# MI0283QT_v15.net
KiCad netlist of a schematic drawn in EAGLE
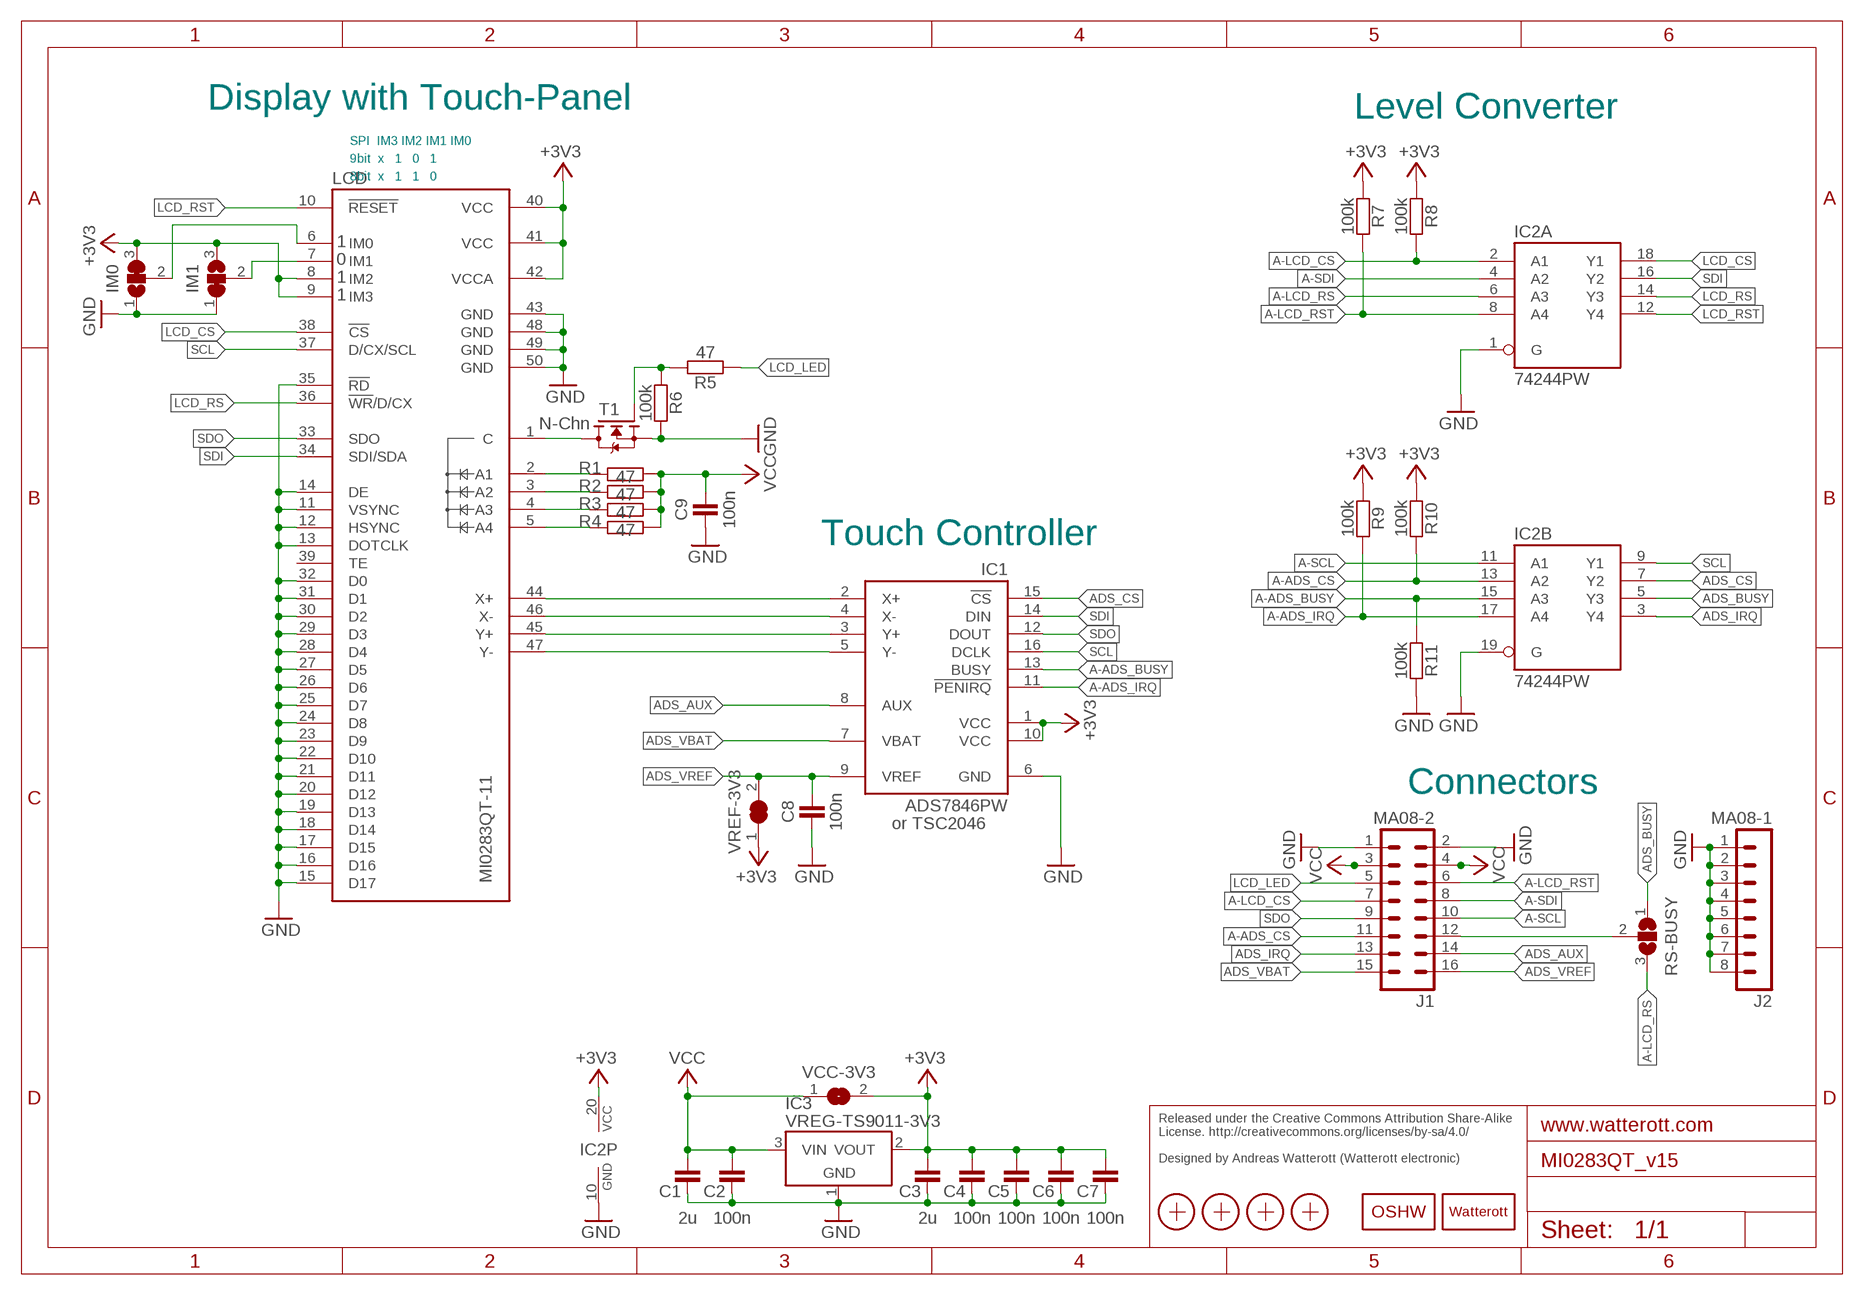
[diagram p0: schematic, sheet 1]

(export (version "E")
  (design (tool "Eeschema 10.0.6"))
  (components
    (comp (ref "C1")
      (value "2u")
      (footprint "eagle-import:C0603")
      (libsource (lib "eagle-import") (part "CAPACITOR-0603"))
    )
    (comp (ref "C2")
      (value "100n")
      (footprint "eagle-import:C0402")
      (libsource (lib "eagle-import") (part "CAPACITOR-0402"))
    )
    (comp (ref "C3")
      (value "2u")
      (footprint "eagle-import:C0603")
      (libsource (lib "eagle-import") (part "CAPACITOR-0603"))
    )
    (comp (ref "C4")
      (value "100n")
      (footprint "eagle-import:C0402")
      (libsource (lib "eagle-import") (part "CAPACITOR-0402"))
    )
    (comp (ref "C5")
      (value "100n")
      (footprint "eagle-import:C0402")
      (libsource (lib "eagle-import") (part "CAPACITOR-0402"))
    )
    (comp (ref "C6")
      (value "100n")
      (footprint "eagle-import:C0402")
      (libsource (lib "eagle-import") (part "CAPACITOR-0402"))
    )
    (comp (ref "C7")
      (value "100n")
      (footprint "eagle-import:C0402")
      (libsource (lib "eagle-import") (part "CAPACITOR-0402"))
    )
    (comp (ref "C8")
      (value "100n")
      (footprint "eagle-import:C0402")
      (libsource (lib "eagle-import") (part "CAPACITOR-0402"))
    )
    (comp (ref "C9")
      (value "100n")
      (footprint "eagle-import:C0402")
      (libsource (lib "eagle-import") (part "CAPACITOR-0402"))
    )
    (comp (ref "IC1")
      (value "ADS7846PW")
      (footprint "eagle-import:TSSOP16")
      (libsource (lib "eagle-import") (part "ADS7846PW"))
    )
    (comp (ref "IC2")
      (value "74244PW")
      (footprint "eagle-import:TSSOP20")
      (libsource (lib "eagle-import") (part "74244PWLVC"))
    )
    (comp (ref "IC3")
      (value "VREG-TS9011-3V3")
      (footprint "eagle-import:SOT23")
      (libsource (lib "eagle-import") (part "VREG-TS9011-3V3"))
    )
    (comp (ref "IM0")
      (value "JUMPER3-0603")
      (footprint "eagle-import:JUMPER3-0603")
      (libsource (lib "eagle-import") (part "JUMPER3-0603"))
    )
    (comp (ref "IM1")
      (value "JUMPER3-0603")
      (footprint "eagle-import:JUMPER3-0603")
      (libsource (lib "eagle-import") (part "JUMPER3-0603"))
    )
    (comp (ref "J1")
      (value "MA08-2")
      (footprint "eagle-import:MA08-2")
      (libsource (lib "eagle-import") (part "MA08-2"))
    )
    (comp (ref "J2")
      (value "MA08-1")
      (footprint "eagle-import:MA08-1")
      (libsource (lib "eagle-import") (part "MA08-1"))
    )
    (comp (ref "LCD")
      (value "MI0283QT-11")
      (footprint "eagle-import:MI0283QT11")
      (libsource (lib "eagle-import") (part "MI0283QT-11"))
    )
    (comp (ref "LOGO2")
      (value "OSHW_LOGOX0150")
      (footprint "eagle-import:OSHW_6X150")
      (libsource (lib "eagle-import") (part "OSHW_LOGOX0150"))
    )
    (comp (ref "LOGO3")
      (value "LOGO-PLACE")
      (footprint "eagle-import:LOGO_TPLACE")
      (libsource (lib "eagle-import") (part "LOGO-PLACE"))
    )
    (comp (ref "R1")
      (value "47")
      (footprint "eagle-import:C0402")
      (libsource (lib "eagle-import") (part "RESISTOR-0402"))
    )
    (comp (ref "R2")
      (value "47")
      (footprint "eagle-import:C0402")
      (libsource (lib "eagle-import") (part "RESISTOR-0402"))
    )
    (comp (ref "R3")
      (value "47")
      (footprint "eagle-import:C0402")
      (libsource (lib "eagle-import") (part "RESISTOR-0402"))
    )
    (comp (ref "R4")
      (value "47")
      (footprint "eagle-import:C0402")
      (libsource (lib "eagle-import") (part "RESISTOR-0402"))
    )
    (comp (ref "R5")
      (value "47")
      (footprint "eagle-import:C0402")
      (libsource (lib "eagle-import") (part "RESISTOR-0402"))
    )
    (comp (ref "R6")
      (value "100k")
      (footprint "eagle-import:C0402")
      (libsource (lib "eagle-import") (part "RESISTOR-0402"))
    )
    (comp (ref "R7")
      (value "100k")
      (footprint "eagle-import:C0402")
      (libsource (lib "eagle-import") (part "RESISTOR-0402"))
    )
    (comp (ref "R8")
      (value "100k")
      (footprint "eagle-import:C0402")
      (libsource (lib "eagle-import") (part "RESISTOR-0402"))
    )
    (comp (ref "R9")
      (value "100k")
      (footprint "eagle-import:C0402")
      (libsource (lib "eagle-import") (part "RESISTOR-0402"))
    )
    (comp (ref "R10")
      (value "100k")
      (footprint "eagle-import:C0402")
      (libsource (lib "eagle-import") (part "RESISTOR-0402"))
    )
    (comp (ref "R11")
      (value "100k")
      (footprint "eagle-import:C0402")
      (libsource (lib "eagle-import") (part "RESISTOR-0402"))
    )
    (comp (ref "RS-BUSY")
      (value "JUMPER3-0603")
      (footprint "eagle-import:JUMPER3-0603")
      (libsource (lib "eagle-import") (part "JUMPER3-0603"))
    )
    (comp (ref "T1")
      (value "N-Chn")
      (footprint "eagle-import:SOT23")
      (libsource (lib "eagle-import") (part "MOSFET-N-SOT23"))
    )
    (comp (ref "VCC-3V3")
      (value "JUMPER2-0603-NC")
      (footprint "eagle-import:JUMPER2-0603_NC")
      (libsource (lib "eagle-import") (part "JUMPER2-0603-NC"))
    )
    (comp (ref "VREF-3V3")
      (value "JUMPER2-0603-NC")
      (footprint "eagle-import:JUMPER2-0603_NC")
      (libsource (lib "eagle-import") (part "JUMPER2-0603-NC"))
    )
    (comp (ref "X1")
      (value "PASSER-07")
      (footprint "eagle-import:PASSER_07MM")
      (libsource (lib "eagle-import") (part "PASSER-07"))
    )
    (comp (ref "X2")
      (value "PASSER-07")
      (footprint "eagle-import:PASSER_07MM")
      (libsource (lib "eagle-import") (part "PASSER-07"))
    )
    (comp (ref "X3")
      (value "PASSER-07")
      (footprint "eagle-import:PASSER_07MM")
      (libsource (lib "eagle-import") (part "PASSER-07"))
    )
    (comp (ref "X4")
      (value "PASSER-07")
      (footprint "eagle-import:PASSER_07MM")
      (libsource (lib "eagle-import") (part "PASSER-07"))
    )
  )
  (nets
    (net (code "1") (name "+3V3") (class "Default")
      (node (ref "C3") (pin "2") (pinfunction "2_2") (pintype "passive"))
      (node (ref "C4") (pin "2") (pinfunction "2_2") (pintype "passive"))
      (node (ref "C5") (pin "2") (pinfunction "2_2") (pintype "passive"))
      (node (ref "C6") (pin "2") (pinfunction "2_2") (pintype "passive"))
      (node (ref "C7") (pin "2") (pinfunction "2_2") (pintype "passive"))
      (node (ref "IC1") (pin "1") (pinfunction "VCC_1") (pintype "power_in"))
      (node (ref "IC1") (pin "10") (pinfunction "VCC_10") (pintype "power_in"))
      (node (ref "IC2") (pin "20") (pinfunction "VCC_20") (pintype "power_in"))
      (node (ref "IC3") (pin "2") (pinfunction "VOUT_2") (pintype "power_in"))
      (node (ref "IM0") (pin "3") (pinfunction "3_3") (pintype "passive"))
      (node (ref "IM1") (pin "3") (pinfunction "3_3") (pintype "passive"))
      (node (ref "LCD") (pin "40") (pinfunction "VCC_40") (pintype "power_in"))
      (node (ref "LCD") (pin "41") (pinfunction "VCC_41") (pintype "power_in"))
      (node (ref "LCD") (pin "42") (pinfunction "VCCA_42") (pintype "power_in"))
      (node (ref "LCD") (pin "8") (pinfunction "IM2_8") (pintype "input"))
      (node (ref "LCD") (pin "9") (pinfunction "IM3_9") (pintype "input"))
      (node (ref "R10") (pin "1") (pinfunction "1_1") (pintype "passive"))
      (node (ref "R7") (pin "1") (pinfunction "1_1") (pintype "passive"))
      (node (ref "R8") (pin "1") (pinfunction "1_1") (pintype "passive"))
      (node (ref "R9") (pin "1") (pinfunction "1_1") (pintype "passive"))
      (node (ref "VCC-3V3") (pin "2") (pinfunction "2_2") (pintype "passive"))
      (node (ref "VREF-3V3") (pin "1") (pinfunction "1_1") (pintype "passive"))
    )
    (net (code "2") (name "A-ADS_BUSY") (class "Default")
      (node (ref "IC1") (pin "13") (pinfunction "BUSY_13") (pintype "output"))
      (node (ref "IC2") (pin "15") (pinfunction "A3_15") (pintype "input"))
      (node (ref "R11") (pin "1") (pinfunction "1_1") (pintype "passive"))
    )
    (net (code "3") (name "A-ADS_CS") (class "Default")
      (node (ref "IC2") (pin "13") (pinfunction "A2_13") (pintype "input"))
      (node (ref "J1") (pin "11") (pinfunction "11_11") (pintype "passive"))
      (node (ref "R10") (pin "2") (pinfunction "2_2") (pintype "passive"))
    )
    (net (code "4") (name "A-ADS_IRQ") (class "Default")
      (node (ref "IC1") (pin "11") (pinfunction "~{PENIRQ}_11") (pintype "output"))
      (node (ref "IC2") (pin "17") (pinfunction "A4_17") (pintype "input"))
      (node (ref "R9") (pin "2") (pinfunction "2_2") (pintype "passive"))
    )
    (net (code "5") (name "A-LCD_CS") (class "Default")
      (node (ref "IC2") (pin "2") (pinfunction "A1_2") (pintype "input"))
      (node (ref "J1") (pin "7") (pinfunction "7_7") (pintype "passive"))
      (node (ref "R8") (pin "2") (pinfunction "2_2") (pintype "passive"))
    )
    (net (code "6") (name "A-LCD_RS") (class "Default")
      (node (ref "IC2") (pin "6") (pinfunction "A3_6") (pintype "input"))
      (node (ref "RS-BUSY") (pin "3") (pinfunction "3_3") (pintype "passive"))
    )
    (net (code "7") (name "A-LCD_RST") (class "Default")
      (node (ref "IC2") (pin "8") (pinfunction "A4_8") (pintype "input"))
      (node (ref "J1") (pin "6") (pinfunction "6_6") (pintype "passive"))
      (node (ref "R7") (pin "2") (pinfunction "2_2") (pintype "passive"))
    )
    (net (code "8") (name "A-SCL") (class "Default")
      (node (ref "IC2") (pin "11") (pinfunction "A1_11") (pintype "input"))
      (node (ref "J1") (pin "10") (pinfunction "10_10") (pintype "passive"))
    )
    (net (code "9") (name "A-SDI") (class "Default")
      (node (ref "IC2") (pin "4") (pinfunction "A2_4") (pintype "input"))
      (node (ref "J1") (pin "8") (pinfunction "8_8") (pintype "passive"))
    )
    (net (code "10") (name "ADS_AUX") (class "Default")
      (node (ref "IC1") (pin "8") (pinfunction "AUX_8") (pintype "input"))
      (node (ref "J1") (pin "14") (pinfunction "14_14") (pintype "passive"))
    )
    (net (code "11") (name "ADS_BUSY") (class "Default")
      (node (ref "IC2") (pin "5") (pinfunction "Y3_5") (pintype "tri_state"))
      (node (ref "RS-BUSY") (pin "1") (pinfunction "1_1") (pintype "passive"))
    )
    (net (code "12") (name "ADS_CS") (class "Default")
      (node (ref "IC1") (pin "15") (pinfunction "~{CS}_15") (pintype "input"))
      (node (ref "IC2") (pin "7") (pinfunction "Y2_7") (pintype "tri_state"))
    )
    (net (code "13") (name "ADS_IRQ") (class "Default")
      (node (ref "IC2") (pin "3") (pinfunction "Y4_3") (pintype "tri_state"))
      (node (ref "J1") (pin "13") (pinfunction "13_13") (pintype "passive"))
    )
    (net (code "14") (name "ADS_VBAT") (class "Default")
      (node (ref "IC1") (pin "7") (pinfunction "VBAT_7") (pintype "input"))
      (node (ref "J1") (pin "15") (pinfunction "15_15") (pintype "passive"))
    )
    (net (code "15") (name "ADS_VREF") (class "Default")
      (node (ref "C8") (pin "2") (pinfunction "2_2") (pintype "passive"))
      (node (ref "IC1") (pin "9") (pinfunction "VREF_9") (pintype "bidirectional"))
      (node (ref "J1") (pin "16") (pinfunction "16_16") (pintype "passive"))
      (node (ref "VREF-3V3") (pin "2") (pinfunction "2_2") (pintype "passive"))
    )
    (net (code "16") (name "GND") (class "Default")
      (node (ref "C1") (pin "1") (pinfunction "1_1") (pintype "passive"))
      (node (ref "C2") (pin "1") (pinfunction "1_1") (pintype "passive"))
      (node (ref "C3") (pin "1") (pinfunction "1_1") (pintype "passive"))
      (node (ref "C4") (pin "1") (pinfunction "1_1") (pintype "passive"))
      (node (ref "C5") (pin "1") (pinfunction "1_1") (pintype "passive"))
      (node (ref "C6") (pin "1") (pinfunction "1_1") (pintype "passive"))
      (node (ref "C7") (pin "1") (pinfunction "1_1") (pintype "passive"))
      (node (ref "C8") (pin "1") (pinfunction "1_1") (pintype "passive"))
      (node (ref "C9") (pin "1") (pinfunction "1_1") (pintype "passive"))
      (node (ref "IC1") (pin "6") (pinfunction "GND_6") (pintype "power_in"))
      (node (ref "IC2") (pin "1") (pinfunction "G_1") (pintype "input"))
      (node (ref "IC2") (pin "10") (pinfunction "GND_10") (pintype "power_in"))
      (node (ref "IC2") (pin "19") (pinfunction "G_19") (pintype "input"))
      (node (ref "IC3") (pin "1") (pinfunction "GND_1") (pintype "power_in"))
      (node (ref "IM0") (pin "1") (pinfunction "1_1") (pintype "passive"))
      (node (ref "IM1") (pin "1") (pinfunction "1_1") (pintype "passive"))
      (node (ref "J1") (pin "1") (pinfunction "1_1") (pintype "passive"))
      (node (ref "J1") (pin "2") (pinfunction "2_2") (pintype "passive"))
      (node (ref "J2") (pin "1") (pinfunction "1_1") (pintype "passive"))
      (node (ref "J2") (pin "2") (pinfunction "2_2") (pintype "passive"))
      (node (ref "J2") (pin "3") (pinfunction "3_3") (pintype "passive"))
      (node (ref "J2") (pin "4") (pinfunction "4_4") (pintype "passive"))
      (node (ref "J2") (pin "5") (pinfunction "5_5") (pintype "passive"))
      (node (ref "J2") (pin "6") (pinfunction "6_6") (pintype "passive"))
      (node (ref "J2") (pin "7") (pinfunction "7_7") (pintype "passive"))
      (node (ref "J2") (pin "8") (pinfunction "8_8") (pintype "passive"))
      (node (ref "LCD") (pin "11") (pinfunction "VSYNC_11") (pintype "input"))
      (node (ref "LCD") (pin "12") (pinfunction "HSYNC_12") (pintype "input"))
      (node (ref "LCD") (pin "13") (pinfunction "DOTCLK_13") (pintype "input"))
      (node (ref "LCD") (pin "14") (pinfunction "DE_14") (pintype "input"))
      (node (ref "LCD") (pin "15") (pinfunction "D17_15") (pintype "input"))
      (node (ref "LCD") (pin "16") (pinfunction "D16_16") (pintype "input"))
      (node (ref "LCD") (pin "17") (pinfunction "D15_17") (pintype "input"))
      (node (ref "LCD") (pin "18") (pinfunction "D14_18") (pintype "input"))
      (node (ref "LCD") (pin "19") (pinfunction "D13_19") (pintype "input"))
      (node (ref "LCD") (pin "20") (pinfunction "D12_20") (pintype "input"))
      (node (ref "LCD") (pin "21") (pinfunction "D11_21") (pintype "input"))
      (node (ref "LCD") (pin "22") (pinfunction "D10_22") (pintype "input"))
      (node (ref "LCD") (pin "23") (pinfunction "D9_23") (pintype "input"))
      (node (ref "LCD") (pin "24") (pinfunction "D8_24") (pintype "input"))
      (node (ref "LCD") (pin "25") (pinfunction "D7_25") (pintype "input"))
      (node (ref "LCD") (pin "26") (pinfunction "D6_26") (pintype "input"))
      (node (ref "LCD") (pin "27") (pinfunction "D5_27") (pintype "input"))
      (node (ref "LCD") (pin "28") (pinfunction "D4_28") (pintype "input"))
      (node (ref "LCD") (pin "29") (pinfunction "D3_29") (pintype "input"))
      (node (ref "LCD") (pin "30") (pinfunction "D2_30") (pintype "input"))
      (node (ref "LCD") (pin "31") (pinfunction "D1_31") (pintype "input"))
      (node (ref "LCD") (pin "32") (pinfunction "D0_32") (pintype "input"))
      (node (ref "LCD") (pin "35") (pinfunction "~{RD}_35") (pintype "input"))
      (node (ref "LCD") (pin "43") (pinfunction "GND_43") (pintype "power_in"))
      (node (ref "LCD") (pin "48") (pinfunction "GND_48") (pintype "power_in"))
      (node (ref "LCD") (pin "49") (pinfunction "GND_49") (pintype "power_in"))
      (node (ref "LCD") (pin "50") (pinfunction "GND_50") (pintype "power_in"))
      (node (ref "R11") (pin "2") (pinfunction "2_2") (pintype "passive"))
      (node (ref "R6") (pin "2") (pinfunction "2_2") (pintype "passive"))
      (node (ref "T1") (pin "2") (pinfunction "S_2") (pintype "passive"))
    )
    (net (code "17") (name "LCD_CS") (class "Default")
      (node (ref "IC2") (pin "18") (pinfunction "Y1_18") (pintype "tri_state"))
      (node (ref "LCD") (pin "38") (pinfunction "~{CS}_38") (pintype "input"))
    )
    (net (code "18") (name "LCD_LED") (class "Default")
      (node (ref "J1") (pin "5") (pinfunction "5_5") (pintype "passive"))
      (node (ref "R5") (pin "1") (pinfunction "1_1") (pintype "passive"))
    )
    (net (code "19") (name "LCD_RS") (class "Default")
      (node (ref "IC2") (pin "14") (pinfunction "Y3_14") (pintype "tri_state"))
      (node (ref "LCD") (pin "36") (pinfunction "~{WR}/D/CX_36") (pintype "input"))
    )
    (net (code "20") (name "LCD_RST") (class "Default")
      (node (ref "IC2") (pin "12") (pinfunction "Y4_12") (pintype "tri_state"))
      (node (ref "LCD") (pin "10") (pinfunction "~{RESET}_10") (pintype "input"))
    )
    (net (code "21") (name "Net-(IC1-X+)") (class "Default")
      (node (ref "IC1") (pin "2") (pinfunction "X+_2") (pintype "input"))
      (node (ref "LCD") (pin "44") (pinfunction "X+_44") (pintype "passive"))
    )
    (net (code "22") (name "Net-(IC1-X-)") (class "Default")
      (node (ref "IC1") (pin "4") (pinfunction "X-_4") (pintype "input"))
      (node (ref "LCD") (pin "46") (pinfunction "X-_46") (pintype "passive"))
    )
    (net (code "23") (name "Net-(IC1-Y+)") (class "Default")
      (node (ref "IC1") (pin "3") (pinfunction "Y+_3") (pintype "input"))
      (node (ref "LCD") (pin "45") (pinfunction "Y+_45") (pintype "passive"))
    )
    (net (code "24") (name "Net-(IC1-Y-)") (class "Default")
      (node (ref "IC1") (pin "5") (pinfunction "Y-_5") (pintype "input"))
      (node (ref "LCD") (pin "47") (pinfunction "Y-_47") (pintype "passive"))
    )
    (net (code "25") (name "Net-(J1-Pad12)") (class "Default")
      (node (ref "J1") (pin "12") (pinfunction "12_12") (pintype "passive"))
      (node (ref "RS-BUSY") (pin "2") (pinfunction "2_2") (pintype "passive"))
    )
    (net (code "26") (name "Net-(LCD-A1)") (class "Default")
      (node (ref "LCD") (pin "2") (pinfunction "A1_2") (pintype "power_in"))
      (node (ref "R1") (pin "2") (pinfunction "2_2") (pintype "passive"))
    )
    (net (code "27") (name "Net-(LCD-A2)") (class "Default")
      (node (ref "LCD") (pin "3") (pinfunction "A2_3") (pintype "power_in"))
      (node (ref "R2") (pin "2") (pinfunction "2_2") (pintype "passive"))
    )
    (net (code "28") (name "Net-(LCD-A3)") (class "Default")
      (node (ref "LCD") (pin "4") (pinfunction "A3_4") (pintype "power_in"))
      (node (ref "R3") (pin "2") (pinfunction "2_2") (pintype "passive"))
    )
    (net (code "29") (name "Net-(LCD-A4)") (class "Default")
      (node (ref "LCD") (pin "5") (pinfunction "A4_5") (pintype "power_in"))
      (node (ref "R4") (pin "2") (pinfunction "2_2") (pintype "passive"))
    )
    (net (code "30") (name "Net-(LCD-C)") (class "Default")
      (node (ref "LCD") (pin "1") (pinfunction "C_1") (pintype "power_in"))
      (node (ref "T1") (pin "3") (pinfunction "D_3") (pintype "passive"))
    )
    (net (code "31") (name "Net-(LCD-IM0)") (class "Default")
      (node (ref "IM0") (pin "2") (pinfunction "2_2") (pintype "passive"))
      (node (ref "LCD") (pin "6") (pinfunction "IM0_6") (pintype "input"))
    )
    (net (code "32") (name "Net-(LCD-IM1)") (class "Default")
      (node (ref "IM1") (pin "2") (pinfunction "2_2") (pintype "passive"))
      (node (ref "LCD") (pin "7") (pinfunction "IM1_7") (pintype "input"))
    )
    (net (code "33") (name "Net-(T1-G)") (class "Default")
      (node (ref "R5") (pin "2") (pinfunction "2_2") (pintype "passive"))
      (node (ref "R6") (pin "1") (pinfunction "1_1") (pintype "passive"))
      (node (ref "T1") (pin "1") (pinfunction "G_1") (pintype "passive"))
    )
    (net (code "34") (name "SCL") (class "Default")
      (node (ref "IC1") (pin "16") (pinfunction "DCLK_16") (pintype "output"))
      (node (ref "IC2") (pin "9") (pinfunction "Y1_9") (pintype "tri_state"))
      (node (ref "LCD") (pin "37") (pinfunction "D/CX/SCL_37") (pintype "input"))
    )
    (net (code "35") (name "SDI") (class "Default")
      (node (ref "IC1") (pin "14") (pinfunction "DIN_14") (pintype "input"))
      (node (ref "IC2") (pin "16") (pinfunction "Y2_16") (pintype "tri_state"))
      (node (ref "LCD") (pin "34") (pinfunction "SDI/SDA_34") (pintype "input"))
    )
    (net (code "36") (name "SDO") (class "Default")
      (node (ref "IC1") (pin "12") (pinfunction "DOUT_12") (pintype "input"))
      (node (ref "J1") (pin "9") (pinfunction "9_9") (pintype "passive"))
      (node (ref "LCD") (pin "33") (pinfunction "SDO_33") (pintype "output"))
    )
    (net (code "37") (name "VCC") (class "Default")
      (node (ref "C1") (pin "2") (pinfunction "2_2") (pintype "passive"))
      (node (ref "C2") (pin "2") (pinfunction "2_2") (pintype "passive"))
      (node (ref "C9") (pin "2") (pinfunction "2_2") (pintype "passive"))
      (node (ref "IC3") (pin "3") (pinfunction "VIN_3") (pintype "power_in"))
      (node (ref "J1") (pin "3") (pinfunction "3_3") (pintype "passive"))
      (node (ref "J1") (pin "4") (pinfunction "4_4") (pintype "passive"))
      (node (ref "R1") (pin "1") (pinfunction "1_1") (pintype "passive"))
      (node (ref "R2") (pin "1") (pinfunction "1_1") (pintype "passive"))
      (node (ref "R3") (pin "1") (pinfunction "1_1") (pintype "passive"))
      (node (ref "R4") (pin "1") (pinfunction "1_1") (pintype "passive"))
      (node (ref "VCC-3V3") (pin "1") (pinfunction "1_1") (pintype "passive"))
    )
    (net (code "38") (name "unconnected-(LCD-TE-Pad39)") (class "Default")
      (node (ref "LCD") (pin "39") (pinfunction "TE_39") (pintype "output"))
    )
  )
)
